# analog_board_fin_proto.net
KiCad netlist of a schematic drawn in EAGLE
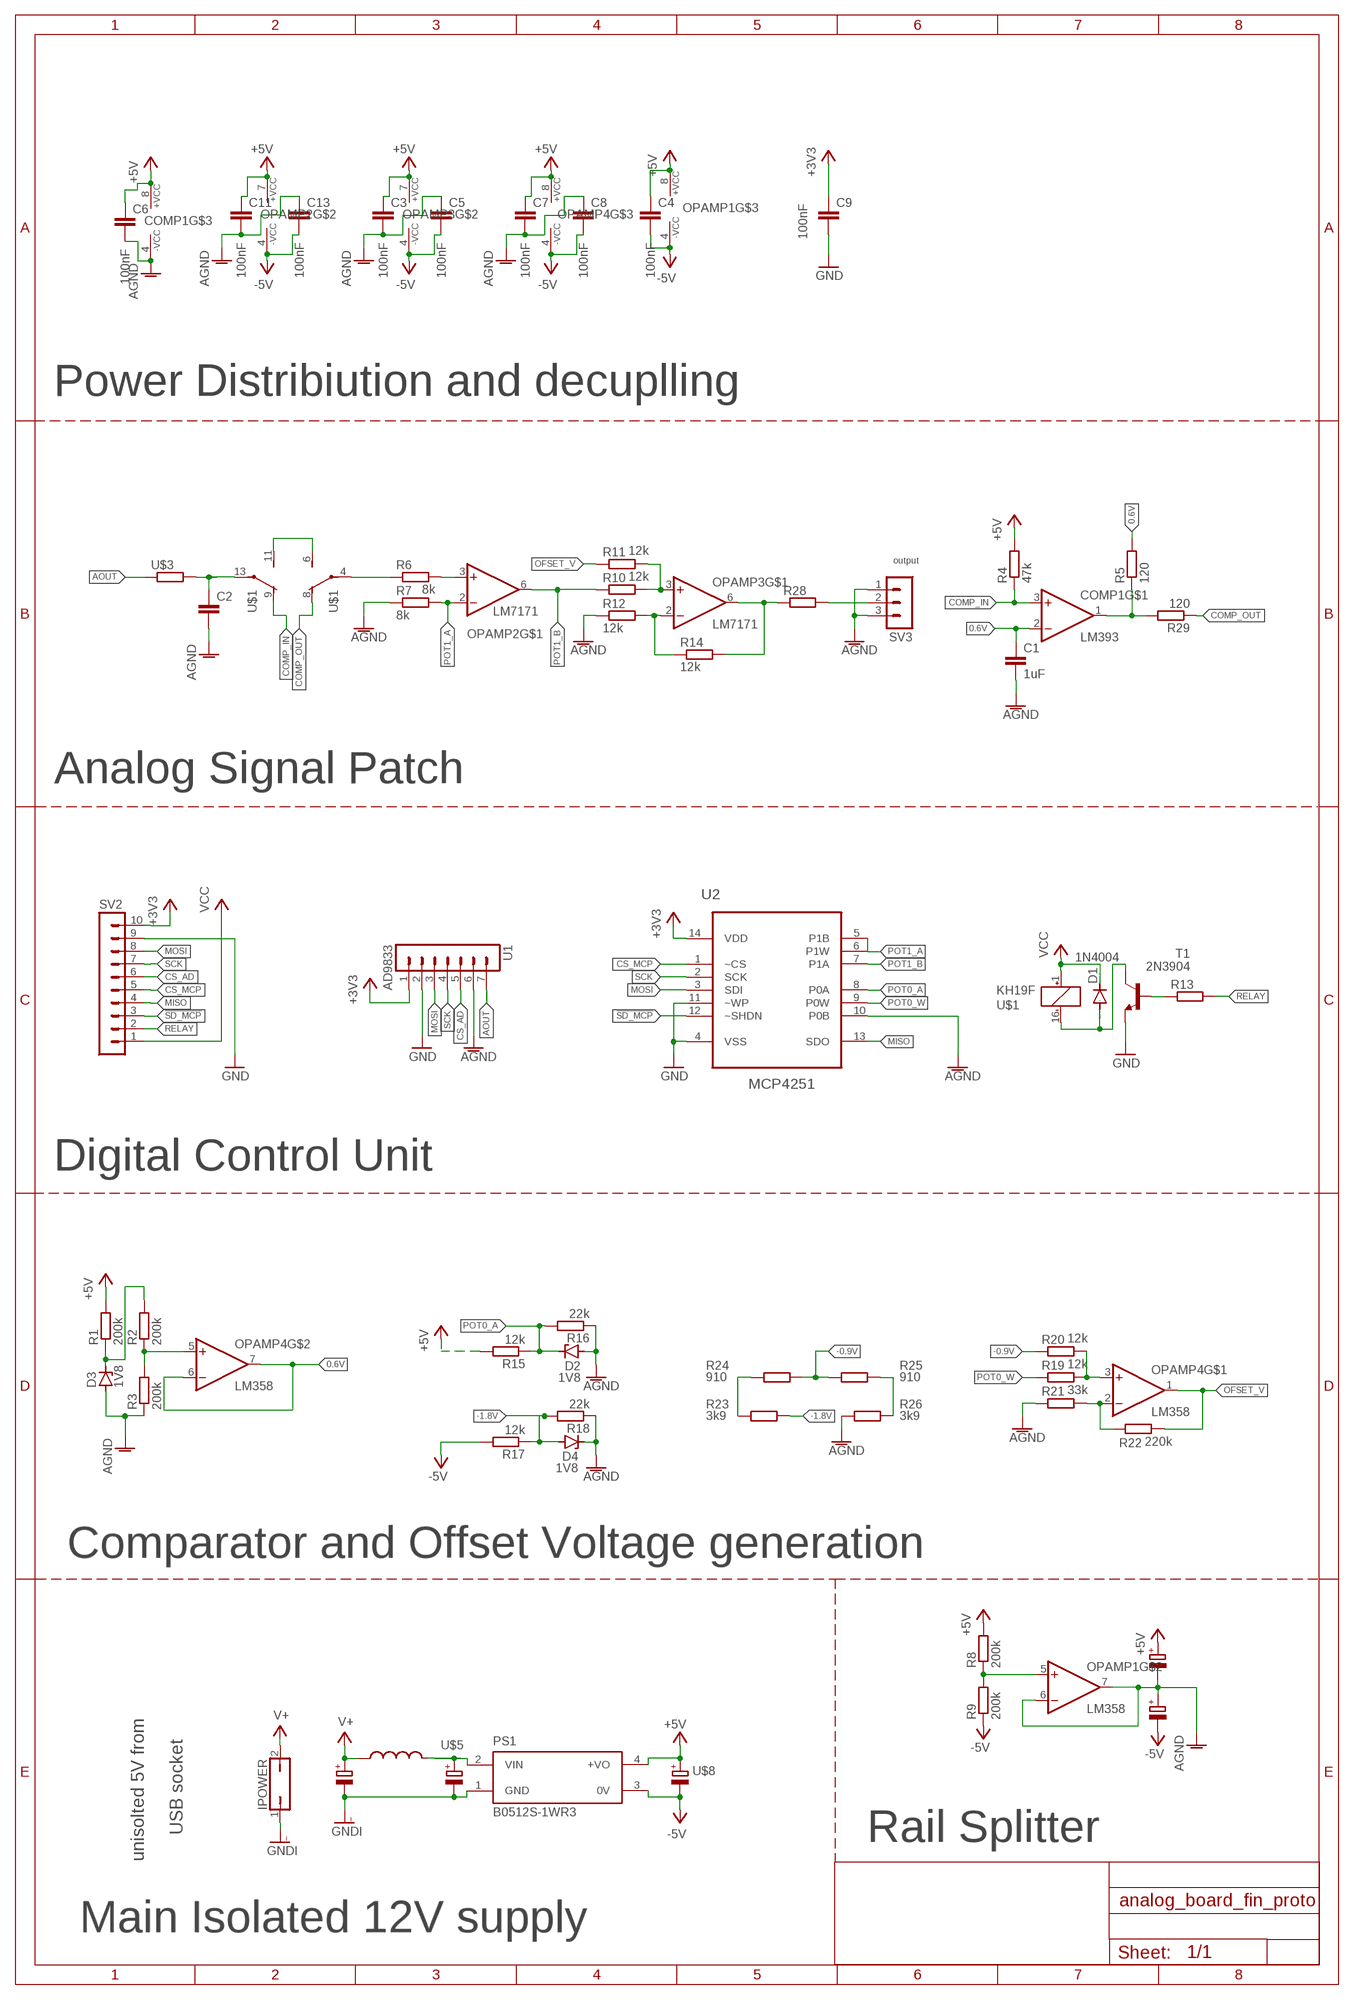
[diagram p0: schematic, sheet 1]

(export (version "E")
  (design (tool "Eeschema 10.0.6"))
  (components
    (comp (ref "C1")
      (value "1uF")
      (footprint "eagle-import:C0805")
      (libsource (lib "eagle-import") (part "C-EUC0805"))
    )
    (comp (ref "C2")
      (value "C-EU025-025X050")
      (footprint "eagle-import:C025-025X050")
      (libsource (lib "eagle-import") (part "C-EU025-025X050"))
    )
    (comp (ref "C3")
      (value "100nF")
      (footprint "eagle-import:C0805")
      (libsource (lib "eagle-import") (part "C-EUC0805"))
    )
    (comp (ref "C4")
      (value "100nF")
      (footprint "eagle-import:C0805")
      (libsource (lib "eagle-import") (part "C-EUC0805"))
    )
    (comp (ref "C5")
      (value "100nF")
      (footprint "eagle-import:C0805")
      (libsource (lib "eagle-import") (part "C-EUC0805"))
    )
    (comp (ref "C6")
      (value "100nF")
      (footprint "eagle-import:C0805")
      (libsource (lib "eagle-import") (part "C-EUC0805"))
    )
    (comp (ref "C7")
      (value "100nF")
      (footprint "eagle-import:C0805")
      (libsource (lib "eagle-import") (part "C-EUC0805"))
    )
    (comp (ref "C8")
      (value "100nF")
      (footprint "eagle-import:C0805")
      (libsource (lib "eagle-import") (part "C-EUC0805"))
    )
    (comp (ref "C9")
      (value "100nF")
      (footprint "eagle-import:C0805")
      (libsource (lib "eagle-import") (part "C-EUC0805"))
    )
    (comp (ref "C11")
      (value "100nF")
      (footprint "eagle-import:C0805")
      (libsource (lib "eagle-import") (part "C-EUC0805"))
    )
    (comp (ref "C13")
      (value "100nF")
      (footprint "eagle-import:C0805")
      (libsource (lib "eagle-import") (part "C-EUC0805"))
    )
    (comp (ref "COMP1")
      (value "LM393")
      (footprint "eagle-import:DIL08")
      (libsource (lib "eagle-import") (part "LM393"))
    )
    (comp (ref "D1")
      (value "1N4004")
      (footprint "eagle-import:DO41-10")
      (libsource (lib "eagle-import") (part "1N4004"))
    )
    (comp (ref "D2")
      (value "1V8")
      (footprint "eagle-import:SOD80C")
      (libsource (lib "eagle-import") (part "ZENER-DIODESOD80C"))
    )
    (comp (ref "D3")
      (value "1V8")
      (footprint "eagle-import:SOD80C")
      (libsource (lib "eagle-import") (part "ZENER-DIODESOD80C"))
    )
    (comp (ref "D4")
      (value "1V8")
      (footprint "eagle-import:SOD80C")
      (libsource (lib "eagle-import") (part "ZENER-DIODESOD80C"))
    )
    (comp (ref "IPOWER")
      (value "POT")
      (footprint "eagle-import:JP1")
      (libsource (lib "eagle-import") (part "JP1Q"))
    )
    (comp (ref "OPAMP1")
      (value "LM358")
      (footprint "eagle-import:DIL08")
      (libsource (lib "eagle-import") (part "LM358"))
    )
    (comp (ref "OPAMP2")
      (value "LM7171")
      (footprint "eagle-import:DIL08")
      (libsource (lib "eagle-import") (part "LM7171"))
    )
    (comp (ref "OPAMP3")
      (value "LM7171")
      (footprint "eagle-import:DIL08")
      (libsource (lib "eagle-import") (part "LM7171"))
    )
    (comp (ref "OPAMP4")
      (value "LM358")
      (footprint "eagle-import:DIL08")
      (libsource (lib "eagle-import") (part "LM358"))
    )
    (comp (ref "PS1")
      (value "B0512S-1WR3")
      (footprint "eagle-import:CONV_B0512S-1WR3")
      (fields (field (name "MF") "Mornsun America, LLC"))
      (libsource (lib "eagle-import") (part "B0512S-1WR3"))
    )
    (comp (ref "R1")
      (value "200k")
      (footprint "eagle-import:R0805")
      (libsource (lib "eagle-import") (part "R-EU_R0805"))
    )
    (comp (ref "R2")
      (value "200k")
      (footprint "eagle-import:R0805")
      (libsource (lib "eagle-import") (part "R-EU_R0805"))
    )
    (comp (ref "R3")
      (value "200k")
      (footprint "eagle-import:R0805")
      (libsource (lib "eagle-import") (part "R-EU_R0805"))
    )
    (comp (ref "R4")
      (value "47k")
      (footprint "eagle-import:R0805")
      (libsource (lib "eagle-import") (part "R-EU_R0805"))
    )
    (comp (ref "R5")
      (value "120")
      (footprint "eagle-import:R0805")
      (libsource (lib "eagle-import") (part "R-EU_R0805"))
    )
    (comp (ref "R6")
      (value "8k")
      (footprint "eagle-import:R0805")
      (libsource (lib "eagle-import") (part "R-EU_R0805"))
    )
    (comp (ref "R7")
      (value "8k")
      (footprint "eagle-import:R0805")
      (libsource (lib "eagle-import") (part "R-EU_R0805"))
    )
    (comp (ref "R8")
      (value "200k")
      (footprint "eagle-import:R0805")
      (libsource (lib "eagle-import") (part "R-EU_R0805"))
    )
    (comp (ref "R9")
      (value "200k")
      (footprint "eagle-import:R0805")
      (libsource (lib "eagle-import") (part "R-EU_R0805"))
    )
    (comp (ref "R10")
      (value "12k")
      (footprint "eagle-import:R0805")
      (libsource (lib "eagle-import") (part "R-EU_R0805"))
    )
    (comp (ref "R11")
      (value "12k")
      (footprint "eagle-import:R0805")
      (libsource (lib "eagle-import") (part "R-EU_R0805"))
    )
    (comp (ref "R12")
      (value "12k")
      (footprint "eagle-import:R0805")
      (libsource (lib "eagle-import") (part "R-EU_R0805"))
    )
    (comp (ref "R13")
      (value "R-EU_R0805")
      (footprint "eagle-import:R0805")
      (libsource (lib "eagle-import") (part "R-EU_R0805"))
    )
    (comp (ref "R14")
      (value "12k")
      (footprint "eagle-import:R0805")
      (libsource (lib "eagle-import") (part "R-EU_R0805"))
    )
    (comp (ref "R15")
      (value "12k")
      (footprint "eagle-import:R0805")
      (libsource (lib "eagle-import") (part "R-EU_R0805"))
    )
    (comp (ref "R16")
      (value "22k")
      (footprint "eagle-import:R0805")
      (libsource (lib "eagle-import") (part "R-EU_R0805"))
    )
    (comp (ref "R17")
      (value "12k")
      (footprint "eagle-import:R0805")
      (libsource (lib "eagle-import") (part "R-EU_R0805"))
    )
    (comp (ref "R18")
      (value "22k")
      (footprint "eagle-import:R0805")
      (libsource (lib "eagle-import") (part "R-EU_R0805"))
    )
    (comp (ref "R19")
      (value "12k")
      (footprint "eagle-import:R0805")
      (libsource (lib "eagle-import") (part "R-EU_R0805"))
    )
    (comp (ref "R20")
      (value "12k")
      (footprint "eagle-import:R0805")
      (libsource (lib "eagle-import") (part "R-EU_R0805"))
    )
    (comp (ref "R21")
      (value "33k")
      (footprint "eagle-import:R0805")
      (libsource (lib "eagle-import") (part "R-EU_R0805"))
    )
    (comp (ref "R22")
      (value "220k")
      (footprint "eagle-import:R0805")
      (libsource (lib "eagle-import") (part "R-EU_R0805"))
    )
    (comp (ref "R23")
      (value "3k9")
      (footprint "eagle-import:R0805")
      (libsource (lib "eagle-import") (part "R-EU_R0805"))
    )
    (comp (ref "R24")
      (value "910")
      (footprint "eagle-import:R0805")
      (libsource (lib "eagle-import") (part "R-EU_R0805"))
    )
    (comp (ref "R25")
      (value "910")
      (footprint "eagle-import:R0805")
      (libsource (lib "eagle-import") (part "R-EU_R0805"))
    )
    (comp (ref "R26")
      (value "3k9")
      (footprint "eagle-import:R0805")
      (libsource (lib "eagle-import") (part "R-EU_R0805"))
    )
    (comp (ref "R28")
      (value "R-EU_R2512")
      (footprint "eagle-import:R2512")
      (libsource (lib "eagle-import") (part "R-EU_R2512"))
    )
    (comp (ref "R29")
      (value "120")
      (footprint "eagle-import:R0805")
      (libsource (lib "eagle-import") (part "R-EU_R0805"))
    )
    (comp (ref "SV2")
      (value "MA10-1")
      (footprint "eagle-import:MA10-1")
      (libsource (lib "eagle-import") (part "MA10-1"))
    )
    (comp (ref "SV3")
      (value "MA03-1")
      (footprint "eagle-import:MA03-1")
      (libsource (lib "eagle-import") (part "MA03-1"))
    )
    (comp (ref "T1")
      (value "2N3904")
      (footprint "eagle-import:TO92")
      (libsource (lib "eagle-import") (part "2N3904"))
    )
    (comp (ref "U$1")
      (value "KH19F")
      (footprint "eagle-import:BT-XX-S")
      (libsource (lib "eagle-import") (part "KH19F"))
    )
    (comp (ref "U$3")
      (value "RESISTOR")
      (footprint "eagle-import:0207_10")
      (libsource (lib "eagle-import") (part "RESISTOR"))
    )
    (comp (ref "U$5")
      (value "CAPACITOR")
      (footprint "eagle-import:E2,5-7")
      (libsource (lib "eagle-import") (part "CAPACITOR"))
    )
    (comp (ref "U$6")
      (value "100nF")
      (footprint "eagle-import:E2,5-7")
      (libsource (lib "eagle-import") (part "CAPACITOR"))
    )
    (comp (ref "U$7")
      (value "INDUCTOR")
      (footprint "eagle-import:0207_10")
      (libsource (lib "eagle-import") (part "INDUCTOR"))
    )
    (comp (ref "U$8")
      (value "CAPACITOR")
      (footprint "eagle-import:E2,5-7")
      (libsource (lib "eagle-import") (part "CAPACITOR"))
    )
    (comp (ref "U$9")
      (value "CAPACITOR")
      (footprint "eagle-import:E2,5-7")
      (libsource (lib "eagle-import") (part "CAPACITOR"))
    )
    (comp (ref "U$10")
      (value "CAPACITOR")
      (footprint "eagle-import:E2,5-7")
      (libsource (lib "eagle-import") (part "CAPACITOR"))
    )
    (comp (ref "U1")
      (value "AD9833")
      (footprint "eagle-import:MA07-1")
      (libsource (lib "eagle-import") (part "MA07-1"))
    )
    (comp (ref "U2")
      (value "MCP4251")
      (footprint "eagle-import:DIL14")
      (libsource (lib "eagle-import") (part "MCP4251"))
    )
  )
  (nets
    (net (code "1") (name "+3V3") (class "Default")
      (node (ref "C9") (pin "1") (pinfunction "1_1") (pintype "passive"))
      (node (ref "SV2") (pin "10") (pinfunction "10_10") (pintype "passive"))
      (node (ref "U1") (pin "1") (pinfunction "1_1") (pintype "passive"))
      (node (ref "U2") (pin "14") (pinfunction "VDD_14") (pintype "power_in"))
    )
    (net (code "2") (name "+5V") (class "Default")
      (node (ref "C11") (pin "1") (pinfunction "1_1") (pintype "passive"))
      (node (ref "C3") (pin "1") (pinfunction "1_1") (pintype "passive"))
      (node (ref "C4") (pin "1") (pinfunction "1_1") (pintype "passive"))
      (node (ref "C6") (pin "1") (pinfunction "1_1") (pintype "passive"))
      (node (ref "C7") (pin "1") (pinfunction "1_1") (pintype "passive"))
      (node (ref "COMP1") (pin "8") (pinfunction "VCC_8") (pintype "power_in"))
      (node (ref "OPAMP1") (pin "8") (pinfunction "VCC_8") (pintype "power_in"))
      (node (ref "OPAMP2") (pin "7") (pinfunction "VCC_7") (pintype "power_in"))
      (node (ref "OPAMP3") (pin "7") (pinfunction "VCC_7") (pintype "power_in"))
      (node (ref "OPAMP4") (pin "8") (pinfunction "VCC_8") (pintype "power_in"))
      (node (ref "PS1") (pin "4") (pinfunction "+VO_4") (pintype "output"))
      (node (ref "R1") (pin "2") (pinfunction "2_2") (pintype "passive"))
      (node (ref "R15") (pin "2") (pinfunction "2_2") (pintype "passive"))
      (node (ref "R4") (pin "2") (pinfunction "2_2") (pintype "passive"))
      (node (ref "R8") (pin "2") (pinfunction "2_2") (pintype "passive"))
      (node (ref "U$8") (pin "+") (pinfunction "+_+") (pintype "passive"))
      (node (ref "U$9") (pin "+") (pinfunction "+_+") (pintype "passive"))
    )
    (net (code "3") (name "-0.9V") (class "Default")
      (node (ref "R20") (pin "1") (pinfunction "1_1") (pintype "passive"))
      (node (ref "R24") (pin "1") (pinfunction "1_1") (pintype "passive"))
      (node (ref "R25") (pin "2") (pinfunction "2_2") (pintype "passive"))
    )
    (net (code "4") (name "-1.8V") (class "Default")
      (node (ref "D4") (pin "A") (pinfunction "A_A") (pintype "passive"))
      (node (ref "R17") (pin "1") (pinfunction "1_1") (pintype "passive"))
      (node (ref "R18") (pin "2") (pinfunction "2_2") (pintype "passive"))
      (node (ref "R23") (pin "2") (pinfunction "2_2") (pintype "passive"))
    )
    (net (code "5") (name "-5V") (class "Default")
      (node (ref "C13") (pin "2") (pinfunction "2_2") (pintype "passive"))
      (node (ref "C4") (pin "2") (pinfunction "2_2") (pintype "passive"))
      (node (ref "C5") (pin "2") (pinfunction "2_2") (pintype "passive"))
      (node (ref "C8") (pin "2") (pinfunction "2_2") (pintype "passive"))
      (node (ref "OPAMP1") (pin "4") (pinfunction "GND_4") (pintype "power_in"))
      (node (ref "OPAMP2") (pin "4") (pinfunction "GND_4") (pintype "power_in"))
      (node (ref "OPAMP3") (pin "4") (pinfunction "GND_4") (pintype "power_in"))
      (node (ref "OPAMP4") (pin "4") (pinfunction "GND_4") (pintype "power_in"))
      (node (ref "PS1") (pin "3") (pinfunction "0V_3") (pintype "passive"))
      (node (ref "R17") (pin "2") (pinfunction "2_2") (pintype "passive"))
      (node (ref "R9") (pin "1") (pinfunction "1_1") (pintype "passive"))
      (node (ref "U$10") (pin "-") (pinfunction "-_-") (pintype "passive"))
      (node (ref "U$8") (pin "-") (pinfunction "-_-") (pintype "passive"))
    )
    (net (code "6") (name "/~{SD_MCP}") (class "Default")
      (node (ref "SV2") (pin "3") (pinfunction "3_3") (pintype "passive"))
      (node (ref "U2") (pin "12") (pinfunction "~{SHDN}_12") (pintype "input"))
    )
    (net (code "7") (name "0.6V") (class "Default")
      (node (ref "C1") (pin "1") (pinfunction "1_1") (pintype "passive"))
      (node (ref "COMP1") (pin "2") (pinfunction "-IN_2") (pintype "input"))
      (node (ref "OPAMP4") (pin "6") (pinfunction "-IN_6") (pintype "input"))
      (node (ref "OPAMP4") (pin "7") (pinfunction "OUT_7") (pintype "output"))
      (node (ref "R5") (pin "2") (pinfunction "2_2") (pintype "passive"))
    )
    (net (code "8") (name "AGND") (class "Default")
      (node (ref "C1") (pin "2") (pinfunction "2_2") (pintype "passive"))
      (node (ref "C11") (pin "2") (pinfunction "2_2") (pintype "passive"))
      (node (ref "C13") (pin "1") (pinfunction "1_1") (pintype "passive"))
      (node (ref "C2") (pin "2") (pinfunction "2_2") (pintype "passive"))
      (node (ref "C3") (pin "2") (pinfunction "2_2") (pintype "passive"))
      (node (ref "C5") (pin "1") (pinfunction "1_1") (pintype "passive"))
      (node (ref "C6") (pin "2") (pinfunction "2_2") (pintype "passive"))
      (node (ref "C7") (pin "2") (pinfunction "2_2") (pintype "passive"))
      (node (ref "C8") (pin "1") (pinfunction "1_1") (pintype "passive"))
      (node (ref "COMP1") (pin "4") (pinfunction "GND_4") (pintype "power_in"))
      (node (ref "D2") (pin "A") (pinfunction "A_A") (pintype "passive"))
      (node (ref "D3") (pin "A") (pinfunction "A_A") (pintype "passive"))
      (node (ref "D4") (pin "C") (pinfunction "C_C") (pintype "passive"))
      (node (ref "OPAMP1") (pin "6") (pinfunction "-IN_6") (pintype "input"))
      (node (ref "OPAMP1") (pin "7") (pinfunction "OUT_7") (pintype "output"))
      (node (ref "R12") (pin "1") (pinfunction "1_1") (pintype "passive"))
      (node (ref "R16") (pin "1") (pinfunction "1_1") (pintype "passive"))
      (node (ref "R18") (pin "1") (pinfunction "1_1") (pintype "passive"))
      (node (ref "R21") (pin "1") (pinfunction "1_1") (pintype "passive"))
      (node (ref "R26") (pin "1") (pinfunction "1_1") (pintype "passive"))
      (node (ref "R3") (pin "1") (pinfunction "1_1") (pintype "passive"))
      (node (ref "R7") (pin "1") (pinfunction "1_1") (pintype "passive"))
      (node (ref "SV3") (pin "1") (pinfunction "1_1") (pintype "passive"))
      (node (ref "SV3") (pin "3") (pinfunction "3_3") (pintype "passive"))
      (node (ref "U$10") (pin "+") (pinfunction "+_+") (pintype "passive"))
      (node (ref "U$9") (pin "-") (pinfunction "-_-") (pintype "passive"))
      (node (ref "U1") (pin "6") (pinfunction "6_6") (pintype "passive"))
      (node (ref "U2") (pin "10") (pinfunction "P0B_10") (pintype "passive"))
    )
    (net (code "9") (name "AOUT") (class "Default")
      (node (ref "U$3") (pin "1") (pinfunction "1_1") (pintype "passive"))
      (node (ref "U1") (pin "7") (pinfunction "7_7") (pintype "passive"))
    )
    (net (code "10") (name "COMP_IN") (class "Default")
      (node (ref "COMP1") (pin "3") (pinfunction "+IN_3") (pintype "input"))
      (node (ref "R4") (pin "1") (pinfunction "1_1") (pintype "passive"))
      (node (ref "U$1") (pin "9") (pinfunction "O_9") (pintype "passive"))
    )
    (net (code "11") (name "COMP_OUT") (class "Default")
      (node (ref "R29") (pin "1") (pinfunction "1_1") (pintype "passive"))
      (node (ref "U$1") (pin "8") (pinfunction "O_8") (pintype "passive"))
    )
    (net (code "12") (name "CS_AD") (class "Default")
      (node (ref "SV2") (pin "6") (pinfunction "6_6") (pintype "passive"))
      (node (ref "U1") (pin "5") (pinfunction "5_5") (pintype "passive"))
    )
    (net (code "13") (name "CS_MCP") (class "Default")
      (node (ref "SV2") (pin "5") (pinfunction "5_5") (pintype "passive"))
      (node (ref "U2") (pin "1") (pinfunction "~{CS}_1") (pintype "input"))
    )
    (net (code "14") (name "GND") (class "Default")
      (node (ref "C9") (pin "2") (pinfunction "2_2") (pintype "passive"))
      (node (ref "SV2") (pin "9") (pinfunction "9_9") (pintype "passive"))
      (node (ref "T1") (pin "3") (pinfunction "E_3") (pintype "passive"))
      (node (ref "U1") (pin "2") (pinfunction "2_2") (pintype "passive"))
      (node (ref "U2") (pin "11") (pinfunction "~{WP}_11") (pintype "input"))
      (node (ref "U2") (pin "4") (pinfunction "VSS_4") (pintype "power_in"))
    )
    (net (code "15") (name "GNDI") (class "Default")
      (node (ref "IPOWER") (pin "1") (pinfunction "1_1") (pintype "passive"))
      (node (ref "PS1") (pin "1") (pinfunction "GND_1") (pintype "power_in"))
      (node (ref "U$5") (pin "-") (pinfunction "-_-") (pintype "passive"))
      (node (ref "U$6") (pin "-") (pinfunction "-_-") (pintype "passive"))
    )
    (net (code "16") (name "MISO") (class "Default")
      (node (ref "SV2") (pin "4") (pinfunction "4_4") (pintype "passive"))
      (node (ref "U2") (pin "13") (pinfunction "SDO_13") (pintype "output"))
    )
    (net (code "17") (name "MOSI") (class "Default")
      (node (ref "SV2") (pin "8") (pinfunction "8_8") (pintype "passive"))
      (node (ref "U1") (pin "3") (pinfunction "3_3") (pintype "passive"))
      (node (ref "U2") (pin "3") (pinfunction "SDI_3") (pintype "input"))
    )
    (net (code "18") (name "Net-(COMP1A-OUT)") (class "Default")
      (node (ref "COMP1") (pin "1") (pinfunction "OUT_1") (pintype "output"))
      (node (ref "R29") (pin "2") (pinfunction "2_2") (pintype "passive"))
      (node (ref "R5") (pin "1") (pinfunction "1_1") (pintype "passive"))
    )
    (net (code "19") (name "Net-(D3-PadC)") (class "Default")
      (node (ref "D3") (pin "C") (pinfunction "C_C") (pintype "passive"))
      (node (ref "R1") (pin "1") (pinfunction "1_1") (pintype "passive"))
      (node (ref "R2") (pin "2") (pinfunction "2_2") (pintype "passive"))
    )
    (net (code "20") (name "Net-(OPAMP1B-+IN)") (class "Default")
      (node (ref "OPAMP1") (pin "5") (pinfunction "+IN_5") (pintype "input"))
      (node (ref "R8") (pin "1") (pinfunction "1_1") (pintype "passive"))
      (node (ref "R9") (pin "2") (pinfunction "2_2") (pintype "passive"))
    )
    (net (code "21") (name "Net-(OPAMP2A-+IN)") (class "Default")
      (node (ref "OPAMP2") (pin "3") (pinfunction "+IN_3") (pintype "input"))
      (node (ref "R6") (pin "2") (pinfunction "2_2") (pintype "passive"))
    )
    (net (code "22") (name "Net-(OPAMP3A-+IN)") (class "Default")
      (node (ref "OPAMP3") (pin "3") (pinfunction "+IN_3") (pintype "input"))
      (node (ref "R10") (pin "2") (pinfunction "2_2") (pintype "passive"))
      (node (ref "R11") (pin "2") (pinfunction "2_2") (pintype "passive"))
    )
    (net (code "23") (name "Net-(OPAMP3A--IN)") (class "Default")
      (node (ref "OPAMP3") (pin "2") (pinfunction "-IN_2") (pintype "input"))
      (node (ref "R12") (pin "2") (pinfunction "2_2") (pintype "passive"))
      (node (ref "R14") (pin "1") (pinfunction "1_1") (pintype "passive"))
    )
    (net (code "24") (name "Net-(OPAMP3A-OUT)") (class "Default")
      (node (ref "OPAMP3") (pin "6") (pinfunction "OUT_6") (pintype "output"))
      (node (ref "R14") (pin "2") (pinfunction "2_2") (pintype "passive"))
      (node (ref "R28") (pin "1") (pinfunction "1_1") (pintype "passive"))
    )
    (net (code "25") (name "Net-(OPAMP4A-+IN)") (class "Default")
      (node (ref "OPAMP4") (pin "3") (pinfunction "+IN_3") (pintype "input"))
      (node (ref "R19") (pin "2") (pinfunction "2_2") (pintype "passive"))
      (node (ref "R20") (pin "2") (pinfunction "2_2") (pintype "passive"))
    )
    (net (code "26") (name "Net-(OPAMP4A--IN)") (class "Default")
      (node (ref "OPAMP4") (pin "2") (pinfunction "-IN_2") (pintype "input"))
      (node (ref "R21") (pin "2") (pinfunction "2_2") (pintype "passive"))
      (node (ref "R22") (pin "1") (pinfunction "1_1") (pintype "passive"))
    )
    (net (code "27") (name "Net-(OPAMP4B-+IN)") (class "Default")
      (node (ref "OPAMP4") (pin "5") (pinfunction "+IN_5") (pintype "input"))
      (node (ref "R2") (pin "1") (pinfunction "1_1") (pintype "passive"))
      (node (ref "R3") (pin "2") (pinfunction "2_2") (pintype "passive"))
    )
    (net (code "28") (name "Net-(PS1-VIN)") (class "Default")
      (node (ref "PS1") (pin "2") (pinfunction "VIN_2") (pintype "input"))
      (node (ref "U$5") (pin "+") (pinfunction "+_+") (pintype "passive"))
      (node (ref "U$7") (pin "2") (pinfunction "2_2") (pintype "passive"))
    )
    (net (code "29") (name "Net-(R23-Pad1)") (class "Default")
      (node (ref "R23") (pin "1") (pinfunction "1_1") (pintype "passive"))
      (node (ref "R24") (pin "2") (pinfunction "2_2") (pintype "passive"))
    )
    (net (code "30") (name "Net-(R25-Pad1)") (class "Default")
      (node (ref "R25") (pin "1") (pinfunction "1_1") (pintype "passive"))
      (node (ref "R26") (pin "2") (pinfunction "2_2") (pintype "passive"))
    )
    (net (code "31") (name "Net-(R28-Pad2)") (class "Default")
      (node (ref "R28") (pin "2") (pinfunction "2_2") (pintype "passive"))
      (node (ref "SV3") (pin "2") (pinfunction "2_2") (pintype "passive"))
    )
    (net (code "32") (name "Net-(T1-B)") (class "Default")
      (node (ref "R13") (pin "1") (pinfunction "1_1") (pintype "passive"))
      (node (ref "T1") (pin "2") (pinfunction "B_2") (pintype "passive"))
    )
    (net (code "33") (name "Net-(T1-C)") (class "Default")
      (node (ref "D1") (pin "A") (pinfunction "A_A") (pintype "passive"))
      (node (ref "T1") (pin "1") (pinfunction "C_1") (pintype "passive"))
      (node (ref "U$1") (pin "16") (pinfunction "-_16") (pintype "passive"))
    )
    (net (code "34") (name "Net-(U$1B-P)") (class "Default")
      (node (ref "R6") (pin "1") (pinfunction "1_1") (pintype "passive"))
      (node (ref "U$1") (pin "4") (pinfunction "P_4") (pintype "passive"))
    )
    (net (code "35") (name "Net-(U$1B-S)") (class "Default")
      (node (ref "U$1") (pin "11") (pinfunction "S_11") (pintype "passive"))
      (node (ref "U$1") (pin "6") (pinfunction "S_6") (pintype "passive"))
    )
    (net (code "36") (name "Net-(U$1C-P)") (class "Default")
      (node (ref "C2") (pin "1") (pinfunction "1_1") (pintype "passive"))
      (node (ref "U$1") (pin "13") (pinfunction "P_13") (pintype "passive"))
      (node (ref "U$3") (pin "2") (pinfunction "2_2") (pintype "passive"))
    )
    (net (code "37") (name "OFSET_V") (class "Default")
      (node (ref "OPAMP4") (pin "1") (pinfunction "OUT_1") (pintype "output"))
      (node (ref "R11") (pin "1") (pinfunction "1_1") (pintype "passive"))
      (node (ref "R22") (pin "2") (pinfunction "2_2") (pintype "passive"))
    )
    (net (code "38") (name "POT0_A") (class "Default")
      (node (ref "D2") (pin "C") (pinfunction "C_C") (pintype "passive"))
      (node (ref "R15") (pin "1") (pinfunction "1_1") (pintype "passive"))
      (node (ref "R16") (pin "2") (pinfunction "2_2") (pintype "passive"))
      (node (ref "U2") (pin "8") (pinfunction "P0A_8") (pintype "passive"))
    )
    (net (code "39") (name "POT0_W") (class "Default")
      (node (ref "R19") (pin "1") (pinfunction "1_1") (pintype "passive"))
      (node (ref "U2") (pin "9") (pinfunction "P0W_9") (pintype "passive"))
    )
    (net (code "40") (name "POT1_A") (class "Default")
      (node (ref "OPAMP2") (pin "2") (pinfunction "-IN_2") (pintype "input"))
      (node (ref "R7") (pin "2") (pinfunction "2_2") (pintype "passive"))
      (node (ref "U2") (pin "5") (pinfunction "P1B_5") (pintype "passive"))
      (node (ref "U2") (pin "6") (pinfunction "P1W_6") (pintype "passive"))
    )
    (net (code "41") (name "POT1_B") (class "Default")
      (node (ref "OPAMP2") (pin "6") (pinfunction "OUT_6") (pintype "output"))
      (node (ref "R10") (pin "1") (pinfunction "1_1") (pintype "passive"))
      (node (ref "U2") (pin "7") (pinfunction "P1A_7") (pintype "passive"))
    )
    (net (code "42") (name "RELAY") (class "Default")
      (node (ref "R13") (pin "2") (pinfunction "2_2") (pintype "passive"))
      (node (ref "SV2") (pin "2") (pinfunction "2_2") (pintype "passive"))
    )
    (net (code "43") (name "SCK") (class "Default")
      (node (ref "SV2") (pin "7") (pinfunction "7_7") (pintype "passive"))
      (node (ref "U1") (pin "4") (pinfunction "4_4") (pintype "passive"))
      (node (ref "U2") (pin "2") (pinfunction "SCK_2") (pintype "input"))
    )
    (net (code "44") (name "V+") (class "Default")
      (node (ref "IPOWER") (pin "2") (pinfunction "2_2") (pintype "passive"))
      (node (ref "U$6") (pin "+") (pinfunction "+_+") (pintype "passive"))
      (node (ref "U$7") (pin "1") (pinfunction "1_1") (pintype "passive"))
    )
    (net (code "45") (name "VCC") (class "Default")
      (node (ref "D1") (pin "C") (pinfunction "C_C") (pintype "passive"))
      (node (ref "SV2") (pin "1") (pinfunction "1_1") (pintype "passive"))
      (node (ref "U$1") (pin "1") (pinfunction "+_1") (pintype "passive"))
    )
  )
)
